# RelayModule_CAN.net
KiCad netlist of a schematic drawn in Altium Designer
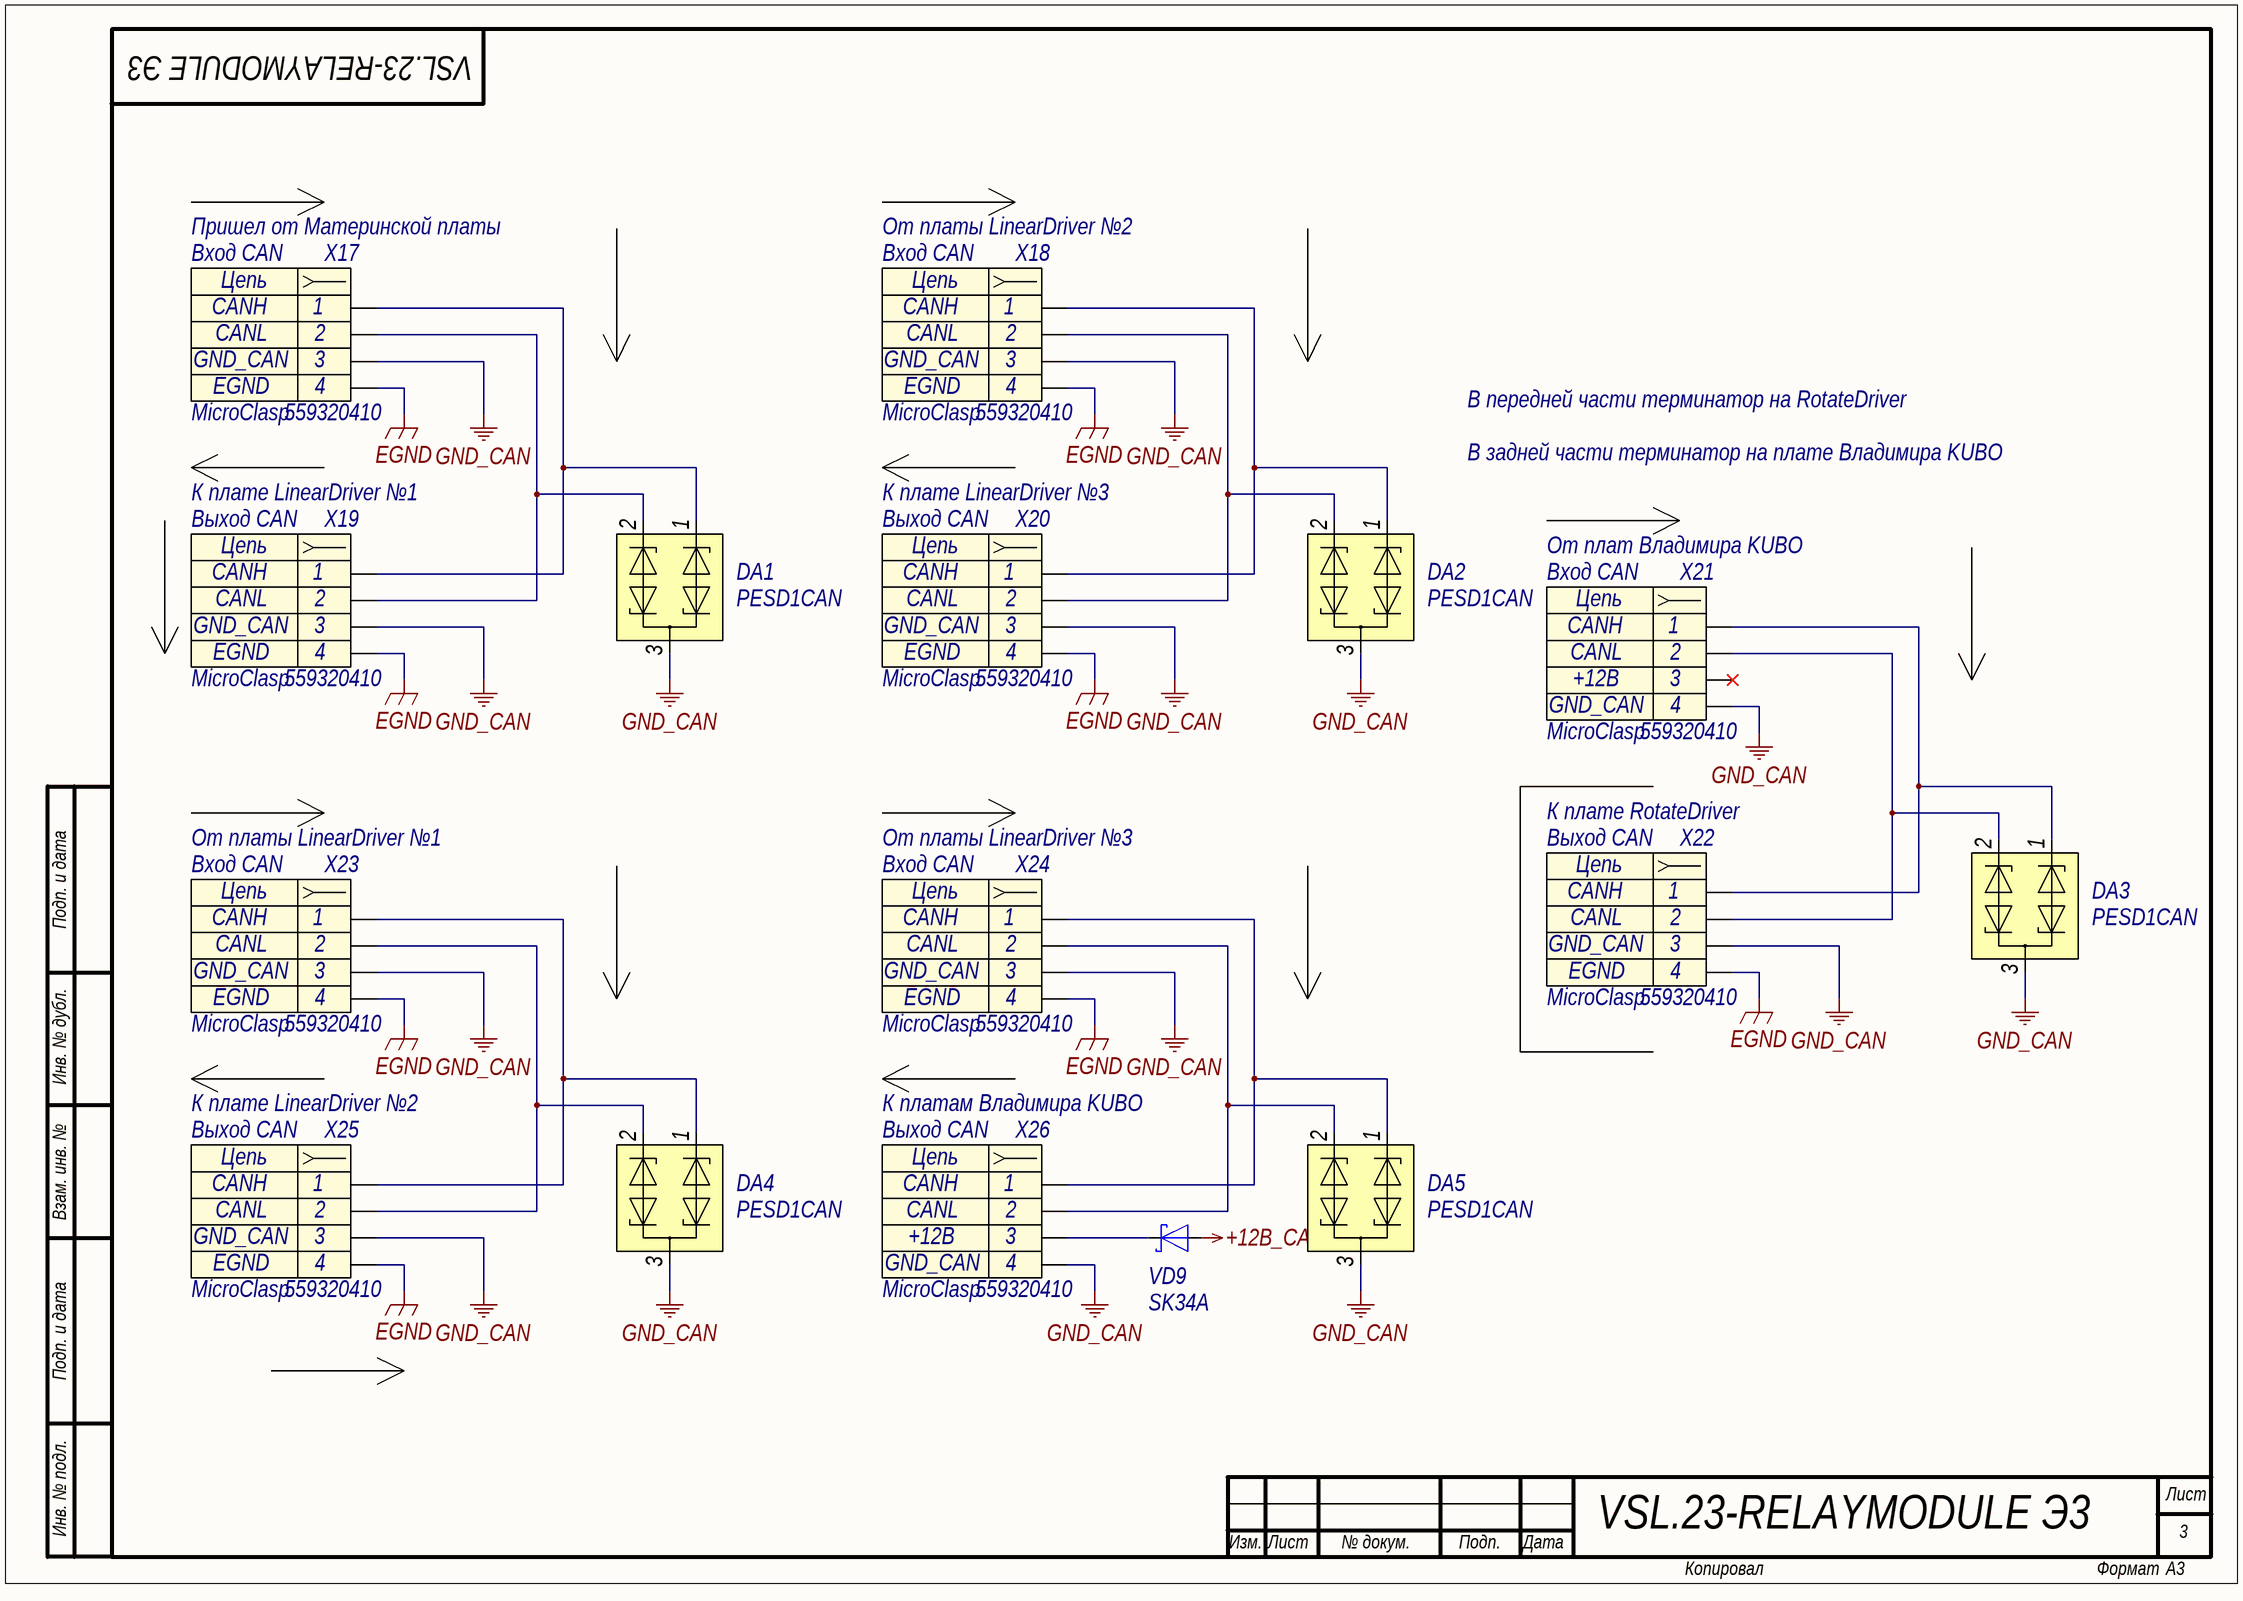
[diagram p0: RelayModule_CAN.SchDoc]

(export (version "E")
  (design (tool "Eeschema 10.0.6"))
  (components
    (comp (ref "DA1")
      (value "PESD")
      (footprint "SOT23-3")
      (description "TVS")
      (fields (field (name "PART NUMBER") "PESD1CAN"))
      (libsource (lib "MOP44") (part "PESD"))
    )
    (comp (ref "DA2")
      (value "PESD")
      (footprint "SOT23-3")
      (description "TVS")
      (fields (field (name "PART NUMBER") "PESD1CAN"))
      (libsource (lib "MOP44") (part "PESD"))
    )
    (comp (ref "DA3")
      (value "PESD")
      (footprint "SOT23-3")
      (description "TVS")
      (fields (field (name "PART NUMBER") "PESD1CAN"))
      (libsource (lib "MOP44") (part "PESD"))
    )
    (comp (ref "DA4")
      (value "PESD")
      (footprint "SOT23-3")
      (description "TVS")
      (fields (field (name "PART NUMBER") "PESD1CAN"))
      (libsource (lib "MOP44") (part "PESD"))
    )
    (comp (ref "DA5")
      (value "PESD")
      (footprint "SOT23-3")
      (description "TVS")
      (fields (field (name "PART NUMBER") "PESD1CAN"))
      (libsource (lib "MOP44") (part "PESD"))
    )
    (comp (ref "VD9")
      (value "DiodeSchottky")
      (footprint "SMA")
      (description "Диод Шоттки")
      (fields (field (name "PART NUMBER") "SK34A"))
      (libsource (lib "MOP44") (part "DiodeSchottky"))
    )
    (comp (ref "X17")
      (value "Вход CAN")
      (footprint "MOLEX_559320410")
      (description "Разъем - 4 конт. розетка")
      (fields (field (name "PART NAME") "MicroClasp") (field (name "PART NUMBER") "559320410"))
      (libsource (lib "MOP44") (part "Header_4_sct"))
    )
    (comp (ref "X18")
      (value "Вход CAN")
      (footprint "MOLEX_559320410")
      (description "Разъем - 4 конт. розетка")
      (fields (field (name "PART NAME") "MicroClasp") (field (name "PART NUMBER") "559320410"))
      (libsource (lib "MOP44") (part "Header_4_sct"))
    )
    (comp (ref "X19")
      (value "Выход CAN")
      (footprint "MOLEX_559320410")
      (description "Разъем - 4 конт. розетка")
      (fields (field (name "PART NAME") "MicroClasp") (field (name "PART NUMBER") "559320410"))
      (libsource (lib "MOP44") (part "Header_4_sct"))
    )
    (comp (ref "X20")
      (value "Выход CAN")
      (footprint "MOLEX_559320410")
      (description "Разъем - 4 конт. розетка")
      (fields (field (name "PART NAME") "MicroClasp") (field (name "PART NUMBER") "559320410"))
      (libsource (lib "MOP44") (part "Header_4_sct"))
    )
    (comp (ref "X21")
      (value "Вход CAN")
      (footprint "MOLEX_559320410")
      (description "Разъем - 4 конт. розетка")
      (fields (field (name "PART NAME") "MicroClasp") (field (name "PART NUMBER") "559320410"))
      (libsource (lib "MOP44") (part "Header_4_sct"))
    )
    (comp (ref "X22")
      (value "Выход CAN")
      (footprint "MOLEX_559320410")
      (description "Разъем - 4 конт. розетка")
      (fields (field (name "PART NAME") "MicroClasp") (field (name "PART NUMBER") "559320410"))
      (libsource (lib "MOP44") (part "Header_4_sct"))
    )
    (comp (ref "X23")
      (value "Вход CAN")
      (footprint "MOLEX_559320410")
      (description "Разъем - 4 конт. розетка")
      (fields (field (name "PART NAME") "MicroClasp") (field (name "PART NUMBER") "559320410"))
      (libsource (lib "MOP44") (part "Header_4_sct"))
    )
    (comp (ref "X24")
      (value "Вход CAN")
      (footprint "MOLEX_559320410")
      (description "Разъем - 4 конт. розетка")
      (fields (field (name "PART NAME") "MicroClasp") (field (name "PART NUMBER") "559320410"))
      (libsource (lib "MOP44") (part "Header_4_sct"))
    )
    (comp (ref "X25")
      (value "Выход CAN")
      (footprint "MOLEX_559320410")
      (description "Разъем - 4 конт. розетка")
      (fields (field (name "PART NAME") "MicroClasp") (field (name "PART NUMBER") "559320410"))
      (libsource (lib "MOP44") (part "Header_4_sct"))
    )
    (comp (ref "X26")
      (value "Выход CAN")
      (footprint "MOLEX_559320410")
      (description "Разъем - 4 конт. розетка")
      (fields (field (name "PART NAME") "MicroClasp") (field (name "PART NUMBER") "559320410"))
      (libsource (lib "MOP44") (part "Header_4_sct"))
    )
  )
  (nets
    (net (code "1") (name "+12B_CAN") (class "Default")
      (node (ref "VD9") (pin "2") (pinfunction "A_2") (pintype "passive"))
    )
    (net (code "2") (name "EGND") (class "Default")
      (node (ref "X17") (pin "4") (pinfunction "4_4") (pintype "passive"))
      (node (ref "X18") (pin "4") (pinfunction "4_4") (pintype "passive"))
      (node (ref "X19") (pin "4") (pinfunction "4_4") (pintype "passive"))
      (node (ref "X20") (pin "4") (pinfunction "4_4") (pintype "passive"))
      (node (ref "X22") (pin "4") (pinfunction "4_4") (pintype "passive"))
      (node (ref "X23") (pin "4") (pinfunction "4_4") (pintype "passive"))
      (node (ref "X24") (pin "4") (pinfunction "4_4") (pintype "passive"))
      (node (ref "X25") (pin "4") (pinfunction "4_4") (pintype "passive"))
    )
    (net (code "3") (name "GND_CAN") (class "Default")
      (node (ref "DA1") (pin "3") (pintype "passive"))
      (node (ref "DA2") (pin "3") (pintype "passive"))
      (node (ref "DA3") (pin "3") (pintype "passive"))
      (node (ref "DA4") (pin "3") (pintype "passive"))
      (node (ref "DA5") (pin "3") (pintype "passive"))
      (node (ref "X17") (pin "3") (pinfunction "3_3") (pintype "passive"))
      (node (ref "X18") (pin "3") (pinfunction "3_3") (pintype "passive"))
      (node (ref "X19") (pin "3") (pinfunction "3_3") (pintype "passive"))
      (node (ref "X20") (pin "3") (pinfunction "3_3") (pintype "passive"))
      (node (ref "X21") (pin "4") (pinfunction "4_4") (pintype "passive"))
      (node (ref "X22") (pin "3") (pinfunction "3_3") (pintype "passive"))
      (node (ref "X23") (pin "3") (pinfunction "3_3") (pintype "passive"))
      (node (ref "X24") (pin "3") (pinfunction "3_3") (pintype "passive"))
      (node (ref "X25") (pin "3") (pinfunction "3_3") (pintype "passive"))
      (node (ref "X26") (pin "4") (pinfunction "4_4") (pintype "passive"))
    )
    (net (code "4") (name "Net-(DA1-1)") (class "Default")
      (node (ref "DA1") (pin "2") (pinfunction "1_2") (pintype "passive"))
      (node (ref "X17") (pin "2") (pinfunction "2_2") (pintype "passive"))
      (node (ref "X19") (pin "2") (pinfunction "2_2") (pintype "passive"))
    )
    (net (code "5") (name "Net-(DA1-Pad1)") (class "Default")
      (node (ref "DA1") (pin "1") (pintype "passive"))
      (node (ref "X17") (pin "1") (pinfunction "1_1") (pintype "passive"))
      (node (ref "X19") (pin "1") (pinfunction "1_1") (pintype "passive"))
    )
    (net (code "6") (name "Net-(DA2-1)") (class "Default")
      (node (ref "DA2") (pin "2") (pinfunction "1_2") (pintype "passive"))
      (node (ref "X18") (pin "2") (pinfunction "2_2") (pintype "passive"))
      (node (ref "X20") (pin "2") (pinfunction "2_2") (pintype "passive"))
    )
    (net (code "7") (name "Net-(DA2-Pad1)") (class "Default")
      (node (ref "DA2") (pin "1") (pintype "passive"))
      (node (ref "X18") (pin "1") (pinfunction "1_1") (pintype "passive"))
      (node (ref "X20") (pin "1") (pinfunction "1_1") (pintype "passive"))
    )
    (net (code "8") (name "Net-(DA3-1)") (class "Default")
      (node (ref "DA3") (pin "2") (pinfunction "1_2") (pintype "passive"))
      (node (ref "X21") (pin "2") (pinfunction "2_2") (pintype "passive"))
      (node (ref "X22") (pin "2") (pinfunction "2_2") (pintype "passive"))
    )
    (net (code "9") (name "Net-(DA3-Pad1)") (class "Default")
      (node (ref "DA3") (pin "1") (pintype "passive"))
      (node (ref "X21") (pin "1") (pinfunction "1_1") (pintype "passive"))
      (node (ref "X22") (pin "1") (pinfunction "1_1") (pintype "passive"))
    )
    (net (code "10") (name "Net-(DA4-1)") (class "Default")
      (node (ref "DA4") (pin "2") (pinfunction "1_2") (pintype "passive"))
      (node (ref "X23") (pin "2") (pinfunction "2_2") (pintype "passive"))
      (node (ref "X25") (pin "2") (pinfunction "2_2") (pintype "passive"))
    )
    (net (code "11") (name "Net-(DA4-Pad1)") (class "Default")
      (node (ref "DA4") (pin "1") (pintype "passive"))
      (node (ref "X23") (pin "1") (pinfunction "1_1") (pintype "passive"))
      (node (ref "X25") (pin "1") (pinfunction "1_1") (pintype "passive"))
    )
    (net (code "12") (name "Net-(DA5-1)") (class "Default")
      (node (ref "DA5") (pin "2") (pinfunction "1_2") (pintype "passive"))
      (node (ref "X24") (pin "2") (pinfunction "2_2") (pintype "passive"))
      (node (ref "X26") (pin "2") (pinfunction "2_2") (pintype "passive"))
    )
    (net (code "13") (name "Net-(DA5-Pad1)") (class "Default")
      (node (ref "DA5") (pin "1") (pintype "passive"))
      (node (ref "X24") (pin "1") (pinfunction "1_1") (pintype "passive"))
      (node (ref "X26") (pin "1") (pinfunction "1_1") (pintype "passive"))
    )
    (net (code "14") (name "Net-(VD9-K)") (class "Default")
      (node (ref "VD9") (pin "1") (pinfunction "K_1") (pintype "passive"))
      (node (ref "X26") (pin "3") (pinfunction "3_3") (pintype "passive"))
    )
    (net (code "15") (name "unconnected-(X21-Pad3)") (class "Default")
      (node (ref "X21") (pin "3") (pinfunction "3_3") (pintype "passive+no_connect"))
    )
  )
)
